# 3_waffling60-NMB_mcu.net
KiCad netlist of a schematic drawn in Altium Designer
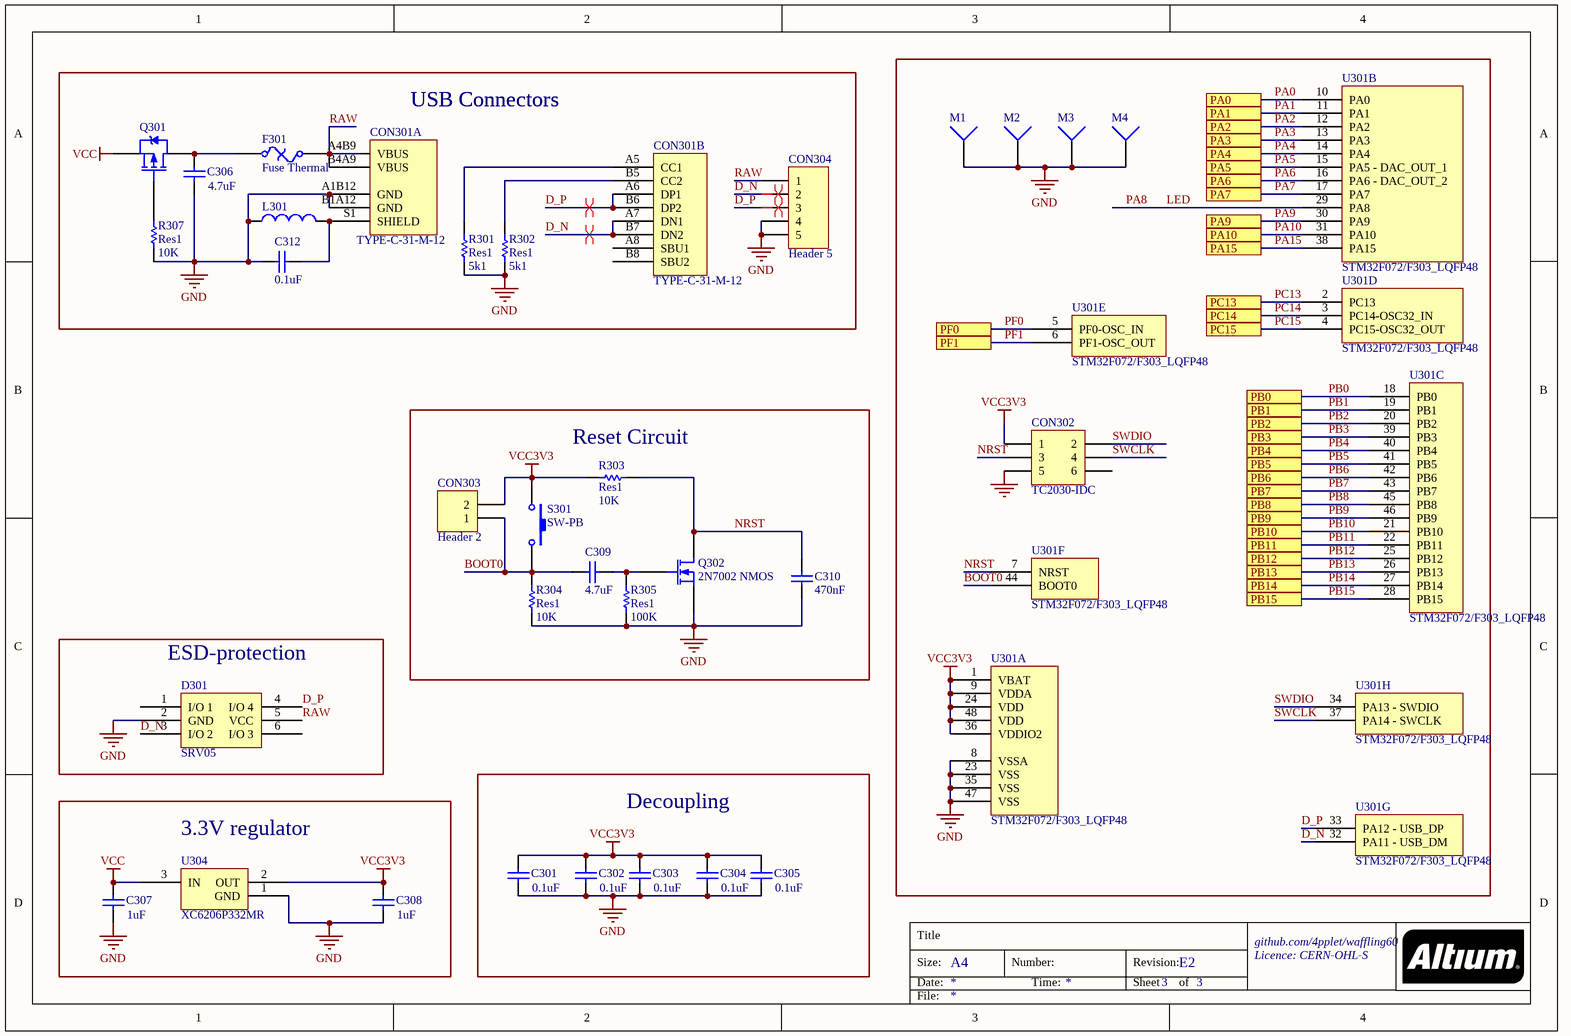
[diagram p0: 3_waffling60-NMB_mcu.SchDoc]

(export (version "E")
  (design (tool "Eeschema 10.0.6"))
  (components
    (comp (ref "C301")
      (value "0.1uF")
      (footprint "C0603[1608]")
      (description "Capacitor")
      (fields (field (name "LCSC PART #") "C14663") (field (name "MRF.PART") "CC0603KRX7R9BB104"))
      (libsource (lib "Miscellaneous Devices") (part "Cap"))
    )
    (comp (ref "C302")
      (value "0.1uF")
      (footprint "C0603[1608]")
      (description "Capacitor")
      (fields (field (name "LCSC PART #") "C14663") (field (name "MRF.PART") "CC0603KRX7R9BB104"))
      (libsource (lib "Miscellaneous Devices") (part "Cap"))
    )
    (comp (ref "C303")
      (value "0.1uF")
      (footprint "C0603[1608]")
      (description "Capacitor")
      (fields (field (name "LCSC PART #") "C14663") (field (name "MRF.PART") "CC0603KRX7R9BB104"))
      (libsource (lib "Miscellaneous Devices") (part "Cap"))
    )
    (comp (ref "C304")
      (value "0.1uF")
      (footprint "C0603[1608]")
      (description "Capacitor")
      (fields (field (name "LCSC PART #") "C14663") (field (name "MRF.PART") "CC0603KRX7R9BB104"))
      (libsource (lib "Miscellaneous Devices") (part "Cap"))
    )
    (comp (ref "C305")
      (value "0.1uF")
      (footprint "C0603[1608]")
      (description "Capacitor")
      (fields (field (name "LCSC PART #") "C14663") (field (name "MRF.PART") "CC0603KRX7R9BB104"))
      (libsource (lib "Miscellaneous Devices") (part "Cap"))
    )
    (comp (ref "C306")
      (value "4.7uF")
      (footprint "C0603[1608]")
      (description "Capacitor")
      (fields (field (name "LCSC PART #") "C19666") (field (name "MRF.PART") "CL10A475KO8NNNC"))
      (libsource (lib "Miscellaneous Devices") (part "Cap"))
    )
    (comp (ref "C307")
      (value "1uF")
      (footprint "C0603[1608]")
      (description "Capacitor")
      (fields (field (name "LCSC PART #") "C15849") (field (name "MRF.PART") "CL10A105KB8NNNC"))
      (libsource (lib "Miscellaneous Devices") (part "Cap"))
    )
    (comp (ref "C308")
      (value "1uF")
      (footprint "C0603[1608]")
      (description "Capacitor")
      (fields (field (name "LCSC PART #") "C15849") (field (name "MRF.PART") "CL10A105KB8NNNC"))
      (libsource (lib "Miscellaneous Devices") (part "Cap"))
    )
    (comp (ref "C309")
      (value "4.7uF")
      (footprint "C0603[1608]")
      (description "Capacitor")
      (fields (field (name "LCSC PART #") "C19666") (field (name "MRF.PART") "CL10A475KO8NNNC"))
      (libsource (lib "Miscellaneous Devices") (part "Cap"))
    )
    (comp (ref "C310")
      (value "470nF")
      (footprint "C0603[1608]")
      (description "Capacitor")
      (fields (field (name "LCSC PART #") "C1623") (field (name "MRF.PART") "CL10B474KA8NNNC"))
      (libsource (lib "Miscellaneous Devices") (part "Cap"))
    )
    (comp (ref "C312")
      (value "0.1uF")
      (footprint "C0603[1608]")
      (description "Capacitor")
      (fields (field (name "LCSC PART #") "C14663") (field (name "MRF.PART") "CC0603KRX7R9BB104"))
      (libsource (lib "Miscellaneous Devices") (part "Cap"))
    )
    (comp (ref "CON301")
      (value "TYPE-C-31-M-12")
      (footprint "TYPE-C-31-M-12")
      (fields (field (name "LCSC PART #") "C165948"))
      (libsource (lib "Schlib1") (part "TYPE-C-31-M-12"))
    )
    (comp (ref "CON302")
      (value "TC2030-IDC")
      (footprint "TC2030-IDC-NL")
      (description "Header, 3-Pin, Dual row")
      (libsource (lib "Miscellaneous Connectors") (part "Header 3X2"))
    )
    (comp (ref "CON303")
      (value "Header 2")
      (footprint "HDR1X2")
      (description "Header, 2-Pin")
      (libsource (lib "Miscellaneous Connectors") (part "Header 2"))
    )
    (comp (ref "CON304")
      (value "Header 5")
      (footprint "JST SM04B-SRSS-TB")
      (description "JST for USB daughter board")
      (fields (field (name "LCSC PART #") "C160404") (field (name "MRF.PART") "SM04B-SRSS-TB(LF)(SN)"))
      (libsource (lib "Miscellaneous Connectors") (part "Header 5"))
    )
    (comp (ref "D301")
      (value "SRV05")
      (footprint "SOT-23-6")
      (fields (field (name "LCSC PART #") "C85364") (field (name "MRF.PART") "SRV05-4-P-T7"))
      (libsource (lib "Keebs") (part "SRV05"))
    )
    (comp (ref "F301")
      (value "Fuse Thermal")
      (footprint "C1206[3216]")
      (description "Thermal Fuse")
      (fields (field (name "LCSC PART #") "C135338") (field (name "MRF.PART") "ASMD1206-050"))
      (libsource (lib "Miscellaneous Devices") (part "Fuse Thermal"))
    )
    (comp (ref "L301")
      (value "Inductor")
      (footprint "L0805")
      (fields (field (name "LCSC PART #") "C1015") (field (name "MRF.PART") "GZ2012D101TF"))
      (libsource (lib "Simulation Generic Components") (part "Inductor"))
    )
    (comp (ref "M1")
      (value "Socket")
      (footprint "mounting_hole")
      (libsource (lib "Miscellaneous Connectors") (part "Socket"))
    )
    (comp (ref "M2")
      (value "Socket")
      (footprint "mounting_hole")
      (libsource (lib "Miscellaneous Connectors") (part "Socket"))
    )
    (comp (ref "M3")
      (value "Socket")
      (footprint "mounting_hole")
      (libsource (lib "Miscellaneous Connectors") (part "Socket"))
    )
    (comp (ref "M4")
      (value "Socket")
      (footprint "mounting_hole")
      (libsource (lib "Miscellaneous Connectors") (part "Socket"))
    )
    (comp (ref "Q301")
      (value "PMOS-2")
      (footprint "SOT-23-3")
      (description "P-Channel Power MOSFET")
      (fields (field (name "LCSC PART #") "C10487") (field (name "MRF.PART") "SI2301CDS-T1-GE3"))
      (libsource (lib "Miscellaneous Devices") (part "PMOS-2"))
    )
    (comp (ref "Q302")
      (value "2N7002 NMOS")
      (footprint "SOT-23-3")
      (description "N-Channel MOSFET")
      (fields (field (name "LCSC PART #") "C8545") (field (name "MRF.PART") "2N7002"))
      (libsource (lib "Miscellaneous Devices") (part "MOSFET-N"))
    )
    (comp (ref "R301")
      (value "Res1")
      (footprint "R0603[1608]")
      (description "Resistor")
      (fields
        (field (name "ALTIUM_VALUE") "5k1")
        (field (name "LCSC PART #") "C23186")
        (field (name "MRF.PART") "0603WAF5101T5E")
      )
      (libsource (lib "Miscellaneous Devices") (part "Res1"))
    )
    (comp (ref "R302")
      (value "Res1")
      (footprint "R0603[1608]")
      (description "Resistor")
      (fields
        (field (name "ALTIUM_VALUE") "5k1")
        (field (name "LCSC PART #") "C23186")
        (field (name "MRF.PART") "0603WAF5101T5E")
      )
      (libsource (lib "Miscellaneous Devices") (part "Res1"))
    )
    (comp (ref "R303")
      (value "Res1")
      (footprint "R0603[1608]")
      (description "Resistor")
      (fields
        (field (name "ALTIUM_VALUE") "10K")
        (field (name "LCSC PART #") "C25804")
        (field (name "MRF.PART") "0603WAF1002T5E")
      )
      (libsource (lib "Miscellaneous Devices") (part "Res1"))
    )
    (comp (ref "R304")
      (value "Res1")
      (footprint "R0603[1608]")
      (description "Resistor")
      (fields
        (field (name "ALTIUM_VALUE") "10K")
        (field (name "LCSC PART #") "C25804")
        (field (name "MRF.PART") "0603WAF1002T5E")
      )
      (libsource (lib "Miscellaneous Devices") (part "Res1"))
    )
    (comp (ref "R305")
      (value "Res1")
      (footprint "R0603[1608]")
      (description "Resistor")
      (fields
        (field (name "ALTIUM_VALUE") "100K")
        (field (name "LCSC PART #") "C25803")
        (field (name "MRF.PART") "0603WAF1003T5E")
      )
      (libsource (lib "Miscellaneous Devices") (part "Res1"))
    )
    (comp (ref "R307")
      (value "Res1")
      (footprint "R0603[1608]")
      (description "Resistor")
      (fields
        (field (name "ALTIUM_VALUE") "10K")
        (field (name "LCSC PART #") "C25804")
        (field (name "MRF.PART") "0603WAF1002T5E")
      )
      (libsource (lib "Miscellaneous Devices") (part "Res1"))
    )
    (comp (ref "S301")
      (value "SW-PB")
      (footprint "XKB Switch")
      (description "Switch")
      (fields (field (name "MRF.PART") "TS-1187A-C-D-B") (field (name "LCSC PART #") "C318888"))
      (libsource (lib "Miscellaneous Devices") (part "SW-PB"))
    )
    (comp (ref "U301")
      (value "STM32F072/F303_LQFP48")
      (footprint "STM32 - COMBO 7X7MM")
      (fields (field (name "LCSC PART #") "C915660") (field (name "MRF.PART") "APM32F072CBT6"))
      (libsource (lib "Keebs") (part "STM32F072/F303_LQFP48"))
    )
    (comp (ref "U304")
      (value "XC6206P332MR")
      (footprint "SOT-23-3")
      (fields (field (name "LCSC PART #") "C5446"))
      (libsource (lib "Keebs") (part "SOT23 LDO"))
    )
  )
  (nets
    (net (code "1") (name "/BOOT0") (class "Default")
      (node (ref "C309") (pin "1") (pinfunction "1_1") (pintype "passive"))
      (node (ref "CON303") (pin "1") (pinfunction "1_1") (pintype "passive"))
      (node (ref "R304") (pin "1") (pinfunction "1_1") (pintype "passive"))
      (node (ref "S301") (pin "2") (pinfunction "2_2") (pintype "passive"))
      (node (ref "U301") (pin "44") (pinfunction "BOOT0_44") (pintype "passive"))
    )
    (net (code "2") (name "/D_N") (class "Default")
      (node (ref "CON301") (pin "A7") (pinfunction "DN1_A7") (pintype "passive"))
      (node (ref "CON301") (pin "B7") (pinfunction "DN2_B7") (pintype "passive"))
      (node (ref "CON304") (pin "2") (pinfunction "2_2") (pintype "passive"))
      (node (ref "D301") (pin "3") (pinfunction "I/O_2_3") (pintype "passive"))
      (node (ref "U301") (pin "32") (pinfunction "PA11_-_USB_DM_32") (pintype "passive"))
    )
    (net (code "3") (name "/D_P") (class "Default")
      (node (ref "CON301") (pin "A6") (pinfunction "DP1_A6") (pintype "passive"))
      (node (ref "CON301") (pin "B6") (pinfunction "DP2_B6") (pintype "passive"))
      (node (ref "CON304") (pin "3") (pinfunction "3_3") (pintype "passive"))
      (node (ref "D301") (pin "4") (pinfunction "I/O_4_4") (pintype "passive"))
      (node (ref "U301") (pin "33") (pinfunction "PA12_-_USB_DP_33") (pintype "passive"))
    )
    (net (code "4") (name "/LED") (class "Default")
      (node (ref "U301") (pin "29") (pinfunction "PA8_29") (pintype "passive"))
    )
    (net (code "5") (name "/NRST") (class "Default")
      (node (ref "C310") (pin "1") (pinfunction "1_1") (pintype "passive"))
      (node (ref "CON302") (pin "3") (pinfunction "3_3") (pintype "passive"))
      (node (ref "Q302") (pin "3") (pinfunction "D_3") (pintype "passive"))
      (node (ref "R303") (pin "2") (pinfunction "2_2") (pintype "passive"))
      (node (ref "U301") (pin "7") (pinfunction "NRST_7") (pintype "passive"))
    )
    (net (code "6") (name "/PA0") (class "Default")
      (node (ref "U301") (pin "10") (pinfunction "PA0_10") (pintype "passive"))
    )
    (net (code "7") (name "/PA1") (class "Default")
      (node (ref "U301") (pin "11") (pinfunction "PA1_11") (pintype "passive"))
    )
    (net (code "8") (name "/PA2") (class "Default")
      (node (ref "U301") (pin "12") (pinfunction "PA2_12") (pintype "passive"))
    )
    (net (code "9") (name "/PA3") (class "Default")
      (node (ref "U301") (pin "13") (pinfunction "PA3_13") (pintype "passive"))
    )
    (net (code "10") (name "/PA4") (class "Default")
      (node (ref "U301") (pin "14") (pinfunction "PA4_14") (pintype "passive"))
    )
    (net (code "11") (name "/PA5") (class "Default")
      (node (ref "U301") (pin "15") (pinfunction "PA5_-_DAC_OUT_1_15") (pintype "passive"))
    )
    (net (code "12") (name "/PA6") (class "Default")
      (node (ref "U301") (pin "16") (pinfunction "PA6_-_DAC_OUT_2_16") (pintype "passive"))
    )
    (net (code "13") (name "/PA7") (class "Default")
      (node (ref "U301") (pin "17") (pinfunction "PA7_17") (pintype "passive"))
    )
    (net (code "14") (name "/PA9") (class "Default")
      (node (ref "U301") (pin "30") (pinfunction "PA9_30") (pintype "passive"))
    )
    (net (code "15") (name "/PA10") (class "Default")
      (node (ref "U301") (pin "31") (pinfunction "PA10_31") (pintype "passive"))
    )
    (net (code "16") (name "/PA15") (class "Default")
      (node (ref "U301") (pin "38") (pinfunction "PA15_38") (pintype "passive"))
    )
    (net (code "17") (name "/PB0") (class "Default")
      (node (ref "U301") (pin "18") (pinfunction "PB0_18") (pintype "passive"))
    )
    (net (code "18") (name "/PB1") (class "Default")
      (node (ref "U301") (pin "19") (pinfunction "PB1_19") (pintype "passive"))
    )
    (net (code "19") (name "/PB2") (class "Default")
      (node (ref "U301") (pin "20") (pinfunction "PB2_20") (pintype "passive"))
    )
    (net (code "20") (name "/PB3") (class "Default")
      (node (ref "U301") (pin "39") (pinfunction "PB3_39") (pintype "passive"))
    )
    (net (code "21") (name "/PB4") (class "Default")
      (node (ref "U301") (pin "40") (pinfunction "PB4_40") (pintype "passive"))
    )
    (net (code "22") (name "/PB5") (class "Default")
      (node (ref "U301") (pin "41") (pinfunction "PB5_41") (pintype "passive"))
    )
    (net (code "23") (name "/PB6") (class "Default")
      (node (ref "U301") (pin "42") (pinfunction "PB6_42") (pintype "passive"))
    )
    (net (code "24") (name "/PB7") (class "Default")
      (node (ref "U301") (pin "43") (pinfunction "PB7_43") (pintype "passive"))
    )
    (net (code "25") (name "/PB8") (class "Default")
      (node (ref "U301") (pin "45") (pinfunction "PB8_45") (pintype "passive"))
    )
    (net (code "26") (name "/PB9") (class "Default")
      (node (ref "U301") (pin "46") (pinfunction "PB9_46") (pintype "passive"))
    )
    (net (code "27") (name "/PB10") (class "Default")
      (node (ref "U301") (pin "21") (pinfunction "PB10_21") (pintype "passive"))
    )
    (net (code "28") (name "/PB11") (class "Default")
      (node (ref "U301") (pin "22") (pinfunction "PB11_22") (pintype "passive"))
    )
    (net (code "29") (name "/PB12") (class "Default")
      (node (ref "U301") (pin "25") (pinfunction "PB12_25") (pintype "passive"))
    )
    (net (code "30") (name "/PB13") (class "Default")
      (node (ref "U301") (pin "26") (pinfunction "PB13_26") (pintype "passive"))
    )
    (net (code "31") (name "/PB14") (class "Default")
      (node (ref "U301") (pin "27") (pinfunction "PB14_27") (pintype "passive"))
    )
    (net (code "32") (name "/PB15") (class "Default")
      (node (ref "U301") (pin "28") (pinfunction "PB15_28") (pintype "passive"))
    )
    (net (code "33") (name "/PC13") (class "Default")
      (node (ref "U301") (pin "2") (pinfunction "PC13_2") (pintype "passive"))
    )
    (net (code "34") (name "/PC14") (class "Default")
      (node (ref "U301") (pin "3") (pinfunction "PC14-OSC32_IN_3") (pintype "passive"))
    )
    (net (code "35") (name "/PC15") (class "Default")
      (node (ref "U301") (pin "4") (pinfunction "PC15-OSC32_OUT_4") (pintype "passive"))
    )
    (net (code "36") (name "/PF0") (class "Default")
      (node (ref "U301") (pin "5") (pinfunction "PF0-OSC_IN_5") (pintype "passive"))
    )
    (net (code "37") (name "/PF1") (class "Default")
      (node (ref "U301") (pin "6") (pinfunction "PF1-OSC_OUT_6") (pintype "passive"))
    )
    (net (code "38") (name "/RAW") (class "Default")
      (node (ref "CON301") (pin "A4B9") (pinfunction "VBUS_A4B9") (pintype "passive"))
      (node (ref "CON301") (pin "B4A9") (pinfunction "VBUS_B4A9") (pintype "passive"))
      (node (ref "CON304") (pin "1") (pinfunction "1_1") (pintype "passive"))
      (node (ref "D301") (pin "5") (pinfunction "VCC_5") (pintype "passive"))
      (node (ref "F301") (pin "2") (pinfunction "2_2") (pintype "passive"))
    )
    (net (code "39") (name "/SWCLK") (class "Default")
      (node (ref "CON302") (pin "4") (pinfunction "4_4") (pintype "passive"))
      (node (ref "U301") (pin "37") (pinfunction "PA14_-_SWCLK_37") (pintype "passive"))
    )
    (net (code "40") (name "/SWDIO") (class "Default")
      (node (ref "CON302") (pin "2") (pinfunction "2_2") (pintype "passive"))
      (node (ref "U301") (pin "34") (pinfunction "PA13_-_SWDIO_34") (pintype "passive"))
    )
    (net (code "41") (name "GND") (class "Default")
      (node (ref "C301") (pin "1") (pinfunction "1_1") (pintype "passive"))
      (node (ref "C302") (pin "1") (pinfunction "1_1") (pintype "passive"))
      (node (ref "C303") (pin "1") (pinfunction "1_1") (pintype "passive"))
      (node (ref "C304") (pin "1") (pinfunction "1_1") (pintype "passive"))
      (node (ref "C305") (pin "1") (pinfunction "1_1") (pintype "passive"))
      (node (ref "C306") (pin "1") (pinfunction "1_1") (pintype "passive"))
      (node (ref "C307") (pin "1") (pinfunction "1_1") (pintype "passive"))
      (node (ref "C308") (pin "1") (pinfunction "1_1") (pintype "passive"))
      (node (ref "C310") (pin "2") (pinfunction "2_2") (pintype "passive"))
      (node (ref "C312") (pin "1") (pinfunction "1_1") (pintype "passive"))
      (node (ref "CON301") (pin "A1B12") (pinfunction "GND_A1B12") (pintype "passive"))
      (node (ref "CON301") (pin "B1A12") (pinfunction "GND_B1A12") (pintype "passive"))
      (node (ref "CON302") (pin "5") (pinfunction "5_5") (pintype "passive"))
      (node (ref "CON304") (pin "4") (pinfunction "4_4") (pintype "passive"))
      (node (ref "CON304") (pin "5") (pinfunction "5_5") (pintype "passive"))
      (node (ref "D301") (pin "2") (pinfunction "GND_2") (pintype "passive"))
      (node (ref "L301") (pin "1") (pinfunction "1_1") (pintype "passive"))
      (node (ref "M1") (pin "1") (pinfunction "1_1") (pintype "passive"))
      (node (ref "M2") (pin "1") (pinfunction "1_1") (pintype "passive"))
      (node (ref "M3") (pin "1") (pinfunction "1_1") (pintype "passive"))
      (node (ref "M4") (pin "1") (pinfunction "1_1") (pintype "passive"))
      (node (ref "Q302") (pin "2") (pinfunction "S_2") (pintype "passive"))
      (node (ref "R301") (pin "2") (pinfunction "2_2") (pintype "passive"))
      (node (ref "R302") (pin "2") (pinfunction "2_2") (pintype "passive"))
      (node (ref "R304") (pin "2") (pinfunction "2_2") (pintype "passive"))
      (node (ref "R305") (pin "2") (pinfunction "2_2") (pintype "passive"))
      (node (ref "R307") (pin "2") (pinfunction "2_2") (pintype "passive"))
      (node (ref "U301") (pin "23") (pinfunction "VSS_23") (pintype "passive"))
      (node (ref "U301") (pin "35") (pinfunction "VSS_35") (pintype "passive"))
      (node (ref "U301") (pin "47") (pinfunction "VSS_47") (pintype "passive"))
      (node (ref "U301") (pin "8") (pinfunction "VSSA_8") (pintype "passive"))
      (node (ref "U304") (pin "1") (pinfunction "GND_1") (pintype "passive"))
    )
    (net (code "42") (name "Net-(CON301A-SHIELD)") (class "Default")
      (node (ref "C312") (pin "2") (pinfunction "2_2") (pintype "passive"))
      (node (ref "CON301") (pin "S1") (pinfunction "SHIELD_S1") (pintype "passive"))
      (node (ref "L301") (pin "2") (pinfunction "2_2") (pintype "passive"))
    )
    (net (code "43") (name "Net-(CON301B-CC1)") (class "Default")
      (node (ref "CON301") (pin "A5") (pinfunction "CC1_A5") (pintype "passive"))
      (node (ref "R301") (pin "1") (pinfunction "1_1") (pintype "passive"))
    )
    (net (code "44") (name "Net-(CON301B-CC2)") (class "Default")
      (node (ref "CON301") (pin "B5") (pinfunction "CC2_B5") (pintype "passive"))
      (node (ref "R302") (pin "1") (pinfunction "1_1") (pintype "passive"))
    )
    (net (code "45") (name "Net-(Q301-D)") (class "Default")
      (node (ref "C306") (pin "2") (pinfunction "2_2") (pintype "passive"))
      (node (ref "F301") (pin "1") (pinfunction "1_1") (pintype "passive"))
      (node (ref "Q301") (pin "3") (pinfunction "D_3") (pintype "passive"))
    )
    (net (code "46") (name "Net-(Q301-G)") (class "Default")
      (node (ref "Q301") (pin "1") (pinfunction "G_1") (pintype "passive"))
      (node (ref "R307") (pin "1") (pinfunction "1_1") (pintype "passive"))
    )
    (net (code "47") (name "Net-(Q302-G)") (class "Default")
      (node (ref "C309") (pin "2") (pinfunction "2_2") (pintype "passive"))
      (node (ref "Q302") (pin "1") (pinfunction "G_1") (pintype "passive"))
      (node (ref "R305") (pin "1") (pinfunction "1_1") (pintype "passive"))
    )
    (net (code "48") (name "VCC") (class "Default")
      (node (ref "C307") (pin "2") (pinfunction "2_2") (pintype "passive"))
      (node (ref "Q301") (pin "2") (pinfunction "S_2") (pintype "passive"))
      (node (ref "U304") (pin "3") (pinfunction "IN_3") (pintype "passive"))
    )
    (net (code "49") (name "VCC3V3") (class "Default")
      (node (ref "C301") (pin "2") (pinfunction "2_2") (pintype "passive"))
      (node (ref "C302") (pin "2") (pinfunction "2_2") (pintype "passive"))
      (node (ref "C303") (pin "2") (pinfunction "2_2") (pintype "passive"))
      (node (ref "C304") (pin "2") (pinfunction "2_2") (pintype "passive"))
      (node (ref "C305") (pin "2") (pinfunction "2_2") (pintype "passive"))
      (node (ref "C308") (pin "2") (pinfunction "2_2") (pintype "passive"))
      (node (ref "CON302") (pin "1") (pinfunction "1_1") (pintype "passive"))
      (node (ref "CON303") (pin "2") (pinfunction "2_2") (pintype "passive"))
      (node (ref "R303") (pin "1") (pinfunction "1_1") (pintype "passive"))
      (node (ref "S301") (pin "1") (pinfunction "1_1") (pintype "passive"))
      (node (ref "U301") (pin "1") (pinfunction "VBAT_1") (pintype "passive"))
      (node (ref "U301") (pin "24") (pinfunction "VDD_24") (pintype "passive"))
      (node (ref "U301") (pin "36") (pinfunction "VDDIO2_36") (pintype "passive"))
      (node (ref "U301") (pin "48") (pinfunction "VDD_48") (pintype "passive"))
      (node (ref "U301") (pin "9") (pinfunction "VDDA_9") (pintype "passive"))
      (node (ref "U304") (pin "2") (pinfunction "OUT_2") (pintype "passive"))
    )
    (net (code "50") (name "unconnected-(CON301B-SBU1-PadA8)") (class "Default")
      (node (ref "CON301") (pin "A8") (pinfunction "SBU1_A8") (pintype "passive"))
    )
    (net (code "51") (name "unconnected-(CON301B-SBU2-PadB8)") (class "Default")
      (node (ref "CON301") (pin "B8") (pinfunction "SBU2_B8") (pintype "passive"))
    )
    (net (code "52") (name "unconnected-(CON302-Pad6)") (class "Default")
      (node (ref "CON302") (pin "6") (pinfunction "6_6") (pintype "passive"))
    )
    (net (code "53") (name "unconnected-(D301-I{slash}O_1-Pad1)") (class "Default")
      (node (ref "D301") (pin "1") (pinfunction "I/O_1_1") (pintype "passive"))
    )
    (net (code "54") (name "unconnected-(D301-I{slash}O_3-Pad6)") (class "Default")
      (node (ref "D301") (pin "6") (pinfunction "I/O_3_6") (pintype "passive"))
    )
  )
)
